# external_LD_mounting.net
KiCad netlist of a schematic drawn in Altium Designer
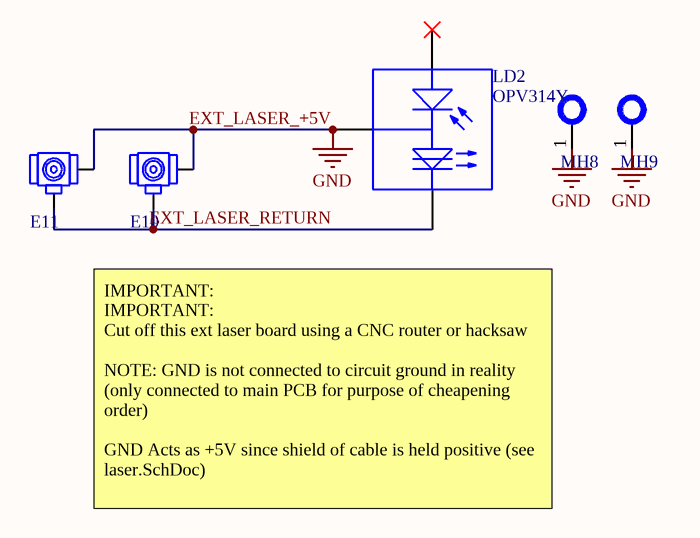
[diagram p0: external_LD_mounting.SchDoc]

(export (version "E")
  (design (tool "Eeschema 10.0.6"))
  (components
    (comp (ref "E10")
      (value "U.FL-R-SMT-1(01)")
      (footprint "HRS-U.FL-R-SMT-3_V 4_LAYER_KO")
      (description "Rf Connectors / Coaxial Connectors SMT Ml Rec Au 50 Ohm W/anti Sldr Wicking UFL")
      (fields (field (name "SOURCE") "UWAA_Stock"))
      (libsource (lib "UWA Aerospace") (part "U.FL Connector"))
    )
    (comp (ref "E11")
      (value "U.FL-R-SMT-1(01)")
      (footprint "HRS-U.FL-R-SMT-3_V 4_LAYER_KO")
      (description "Rf Connectors / Coaxial Connectors SMT Ml Rec Au 50 Ohm W/anti Sldr Wicking UFL")
      (fields (field (name "SOURCE") "UWAA_Stock"))
      (libsource (lib "UWA Aerospace") (part "U.FL Connector"))
    )
    (comp (ref "LD2")
      (value "OPV314Y")
      (footprint "LASER_TO-18")
      (description "VCSEL Emitter, 840nm Min, 860nm Max, 2500Mbps, TO-46, Through Hole Mount")
      (fields (field (name "SOURCE") "Distributor"))
      (libsource (lib "UWA Aerospace") (part "Laser Diode w/ Monitor Photodiode"))
    )
    (comp (ref "MH8")
      (value "Mounting hole M3")
      (footprint "Mounting hole M3-Footprint-1")
      (description "Close fit Di3.2 mm Alt: M3 nut flange")
      (libsource (lib "UWA Aerospace") (part "Hole_NO_BOM"))
    )
    (comp (ref "MH9")
      (value "Mounting hole M3")
      (footprint "Mounting hole M3-Footprint-1")
      (description "Close fit Di3.2 mm Alt: M3 nut flange")
      (libsource (lib "UWA Aerospace") (part "Hole_NO_BOM"))
    )
  )
  (nets
    (net (code "1") (name "/EXT_LASER_RETURN") (class "Default")
      (node (ref "E10") (pin "1") (pinfunction "SIG_1") (pintype "passive"))
      (node (ref "E11") (pin "1") (pinfunction "SIG_1") (pintype "passive"))
      (node (ref "LD2") (pin "1") (pinfunction "LD_K_1") (pintype "passive"))
    )
    (net (code "2") (name "GND") (class "Default")
      (node (ref "E10") (pin "2") (pinfunction "GND_2") (pintype "passive"))
      (node (ref "E11") (pin "2") (pinfunction "GND_2") (pintype "passive"))
      (node (ref "LD2") (pin "2") (pinfunction "COM_2") (pintype "passive"))
      (node (ref "MH8") (pin "1") (pintype "passive"))
      (node (ref "MH9") (pin "1") (pintype "passive"))
    )
    (net (code "3") (name "unconnected-(LD2-PD_A-Pad3)") (class "Default")
      (node (ref "LD2") (pin "3") (pinfunction "PD_A_3") (pintype "passive+no_connect"))
    )
  )
)
